# LEDBlock.net
KiCad netlist of a schematic drawn in Altium Designer
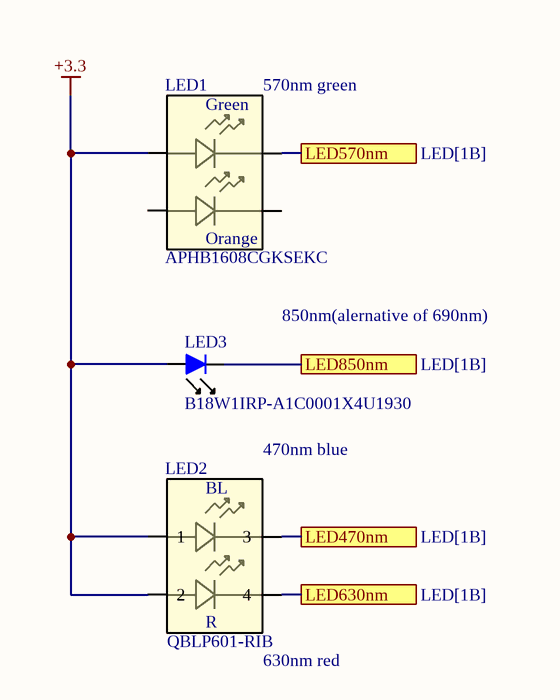
[diagram p0: LEDBlock.SchDoc]

(export (version "E")
  (design (tool "Eeschema 10.0.6"))
  (components
    (comp (ref "LED1")
      (value "APHB1608CGKSEKC")
      (footprint "APHB1608CGKSEKC_KNB")
      (description "Dual Color LED, Super Bright Orange/green, Water Clear, 1.6mm")
      (libsource (lib "Space Concordia") (part "APHB1608CGKSEKC"))
    )
    (comp (ref "LED2")
      (value "QBLP601-RIB")
      (footprint "DFN65P160X55-4N")
      (description "Blue, Red 470nm Blue, 630nm Red LED Indication - Discrete 3.1V Blue, 2V Red 0603 (1608 Metric)")
      (libsource (lib "") (part "New symbol 1_1"))
    )
    (comp (ref "LED3")
      (value "B18W1IRP-A1C0001X4U1930")
      (footprint "CAPCP1608X10N")
      (description "Infrared (IR) Emitter 850nm 1.7V 100mA 23mW/sr @ 100mA (Typ) 80° 0603 (1608 Metric)")
      (libsource (lib "Space Concordia") (part "New symbol 1"))
    )
  )
  (nets
    (net (code "1") (name "+3.3") (class "Default")
      (node (ref "LED1") (pin "1") (pinfunction "1_1") (pintype "passive"))
      (node (ref "LED2") (pin "1") (pinfunction "1_1") (pintype "passive"))
      (node (ref "LED2") (pin "2") (pinfunction "2_2") (pintype "passive"))
      (node (ref "LED3") (pin "2") (pinfunction "A_2") (pintype "passive"))
    )
    (net (code "2") (name "/LED470nm") (class "Default")
      (node (ref "LED2") (pin "3") (pinfunction "3_3") (pintype "passive"))
    )
    (net (code "3") (name "/LED570nm") (class "Default")
      (node (ref "LED1") (pin "2") (pinfunction "2_2") (pintype "passive"))
    )
    (net (code "4") (name "/LED630nm") (class "Default")
      (node (ref "LED2") (pin "4") (pinfunction "4_4") (pintype "passive"))
    )
    (net (code "5") (name "/LED850nm") (class "Default")
      (node (ref "LED3") (pin "1") (pinfunction "K_1") (pintype "passive"))
    )
    (net (code "6") (name "unconnected-(LED1-Pad3)") (class "Default")
      (node (ref "LED1") (pin "3") (pinfunction "3_3") (pintype "passive"))
    )
    (net (code "7") (name "unconnected-(LED1-Pad4)") (class "Default")
      (node (ref "LED1") (pin "4") (pinfunction "4_4") (pintype "passive"))
    )
  )
)
